# Power_FPGA.net
KiCad netlist of a schematic drawn in Altium Designer
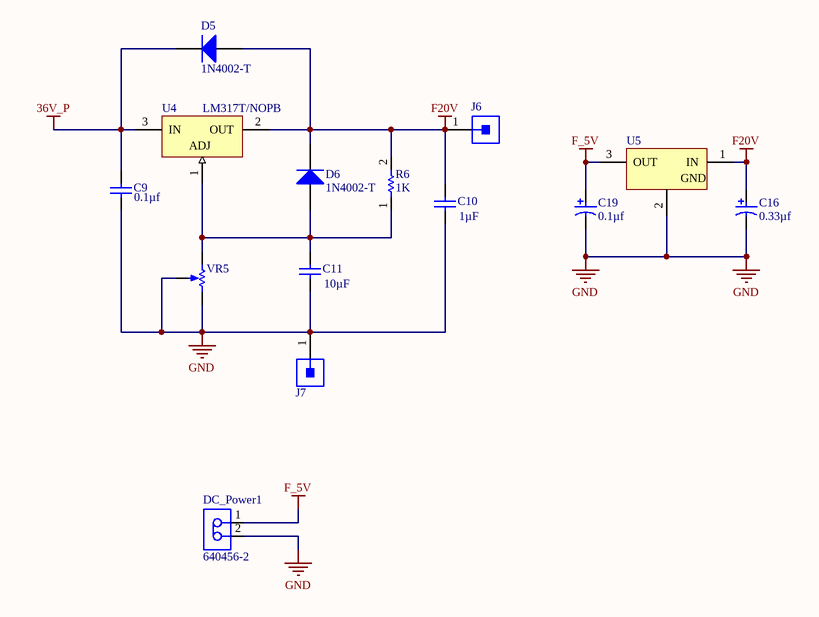
[diagram p0: Power_FPGA.SchDoc]

(export (version "E")
  (design (tool "Eeschema 10.0.6"))
  (components
    (comp (ref "C9")
      (value "0.1µf")
      (footprint "Cap-0.1uf-50V-Ceramic1")
      (description "Lead Capacitor X7R_EIA_ with Capacitance: 0.10F and Rated Voltage: 50Vdc")
      (fields (field (name "MP") "RDER71H104K0K1H03B") (field (name "MF") "Murata"))
      (libsource (lib "YAYAT-LIB") (part "Cap-0.1uf-50V-Ceramic_1"))
    )
    (comp (ref "C10")
      (value "K104K15X7RF5TL2")
      (footprint "Cap-0.1uf-50v-ceramic")
      (description "Ceramic Capacitor, 100 nF, +/- 10%, 50 V, -55 to 125 degC, 2-Pin THD, RoHS, Tape and Reel")
      (fields
        (field (name "MANUFACTURER") "Vishay")
        (field (name "TOLERANCE") "±10%")
        (field (name "CAPACITANCE") "1µF")
      )
      (libsource (lib "YAYAT-LIB") (part "Cap-0.1uf-50v-ceramic"))
    )
    (comp (ref "C11")
      (value "K104K15X7RF5TL2")
      (footprint "Cap-0.1uf-50v-ceramic")
      (description "Ceramic Capacitor, 100 nF, +/- 10%, 50 V, -55 to 125 degC, 2-Pin THD, RoHS, Tape and Reel")
      (fields
        (field (name "MANUFACTURER") "Vishay")
        (field (name "TOLERANCE") "±10%")
        (field (name "CAPACITANCE") "10µF")
      )
      (libsource (lib "YAYAT-LIB") (part "Cap-0.1uf-50v-ceramic"))
    )
    (comp (ref "C16")
      (value "0.33µf")
      (footprint "Cap-1uf-50v-radial")
      (description "Aluminum Electrolytic Capacitor, 1 uF, +/- 20%, 50 V, -55 to 105 degC, 2-Pin THD, RoHS, Bulk")
      (libsource (lib "YAYAT-LIB") (part "Cap-1uf-50v-radial"))
    )
    (comp (ref "C19")
      (value "0.1µf")
      (footprint "Cap-1uf-50v-radial")
      (description "Aluminum Electrolytic Capacitor, 1 uF, +/- 20%, 50 V, -55 to 105 degC, 2-Pin THD, RoHS, Bulk")
      (libsource (lib "YAYAT-LIB") (part "Cap-1uf-50v-radial"))
    )
    (comp (ref "D5")
      (value "1N4002-T")
      (footprint "Diode-1N4002")
      (description "1.0 A Rectifier, 15 pF, 100 V, -65 to 150 degC, 2-Pin DO-41 Plastic, RoHS, Tape and Reel")
      (fields (field (name "MANUFACTURER") "Diodes Inc"))
      (libsource (lib "YAYAT-LIB") (part "Diode-1N4002"))
    )
    (comp (ref "D6")
      (value "1N4002-T")
      (footprint "Diode-1N4002")
      (description "1.0 A Rectifier, 15 pF, 100 V, -65 to 150 degC, 2-Pin DO-41 Plastic, RoHS, Tape and Reel")
      (fields (field (name "MANUFACTURER") "Diodes Inc"))
      (libsource (lib "YAYAT-LIB") (part "Diode-1N4002"))
    )
    (comp (ref "DC_Power1")
      (value "640456-2")
      (footprint "Conn-Wire-header-2pin")
      (fields (field (name "MANUFACTURER") "TE Connectivity"))
      (libsource (lib "YAYAT-LIB") (part "Conn-Wire-header-2pin"))
    )
    (comp (ref "J6")
      (value "61300111121")
      (footprint "PIN-HEADER-1PIN")
      (description "THT Vertical Pin Header WR-PHD, Pitch 2.54 mm, Single Row, 1 pins")
      (fields (field (name "MANUFACTURER") "Wurth Elektronik") (field (name "PUBLISHER") "WurthElektronik"))
      (libsource (lib "") (part "Pin-Header-1Pin_1"))
    )
    (comp (ref "J7")
      (value "61300111121")
      (footprint "PIN-HEADER-1PIN")
      (description "THT Vertical Pin Header WR-PHD, Pitch 2.54 mm, Single Row, 1 pins")
      (fields (field (name "MANUFACTURER") "Wurth Elektronik") (field (name "PUBLISHER") "WurthElektronik"))
      (libsource (lib "YAYAT-LIB") (part "Pin-Header-1Pin"))
    )
    (comp (ref "R6")
      (value "1K")
      (footprint "Resistor-1-Watt")
      (description "Resistor")
      (fields
        (field (name "MANUFACTURER_PART_NUMBER") "OK1025E-R52")
        (field (name "MOUSER PART NUMBER") "588-OK1025E-R52")
      )
      (libsource (lib "YAYAT-LIB") (part "Resistor-1-Watt"))
    )
    (comp (ref "U4")
      (value "LM317T/NOPB")
      (footprint "Voltage-Regulator-LM317")
      (description "3-Terminal Adjustable Regulator, 3-pin TO-220, Pb-Free")
      (fields (field (name "MANUFACTURER") "Texas Instruments"))
      (libsource (lib "YAYAT-LIB") (part "Voltage-Regulator-LM317"))
    )
    (comp (ref "U5")
      (value "L7805ACV")
      (footprint "Voltage-Regulator-L7805ACV")
      (description "Positive Voltage Regulator, 5V, 3-Pin TO-220")
      (libsource (lib "YAYAT-LIB") (part "Voltage-Regulator-L7805ACV"))
    )
    (comp (ref "VR5")
      (value "3296W-1-103LF")
      (footprint "Resistor-Trimmer")
      (fields (field (name "TOLERANCE") "1%"))
      (libsource (lib "YAYAT-LIB") (part "Resistor-Trimmer"))
    )
  )
  (nets
    (net (code "1") (name "36V_P") (class "Default")
      (node (ref "C9") (pin "2") (pinfunction "2_2") (pintype "passive"))
      (node (ref "D5") (pin "2") (pinfunction "K_2") (pintype "passive"))
      (node (ref "U4") (pin "3") (pinfunction "IN_3") (pintype "power_in"))
    )
    (net (code "2") (name "F20V") (class "Default")
      (node (ref "C10") (pin "2") (pinfunction "2_2") (pintype "passive"))
      (node (ref "C16") (pin "1") (pinfunction "1_1") (pintype "passive"))
      (node (ref "D5") (pin "1") (pinfunction "A_1") (pintype "passive"))
      (node (ref "D6") (pin "2") (pinfunction "K_2") (pintype "passive"))
      (node (ref "J6") (pin "1") (pinfunction "1_1") (pintype "passive"))
      (node (ref "R6") (pin "2") (pinfunction "2_2") (pintype "passive"))
      (node (ref "U4") (pin "2") (pinfunction "OUT_2") (pintype "power_in"))
      (node (ref "U5") (pin "1") (pinfunction "IN_1") (pintype "power_in"))
    )
    (net (code "3") (name "F_5V") (class "Default")
      (node (ref "C19") (pin "1") (pinfunction "1_1") (pintype "passive"))
      (node (ref "DC_Power1") (pin "1") (pinfunction "1_1") (pintype "passive"))
      (node (ref "U5") (pin "3") (pinfunction "OUT_3") (pintype "power_in"))
    )
    (net (code "4") (name "GND") (class "Default")
      (node (ref "C10") (pin "1") (pinfunction "1_1") (pintype "passive"))
      (node (ref "C11") (pin "1") (pinfunction "1_1") (pintype "passive"))
      (node (ref "C16") (pin "2") (pinfunction "2_2") (pintype "passive"))
      (node (ref "C19") (pin "2") (pinfunction "2_2") (pintype "passive"))
      (node (ref "C9") (pin "1") (pinfunction "1_1") (pintype "passive"))
      (node (ref "DC_Power1") (pin "2") (pinfunction "2_2") (pintype "passive"))
      (node (ref "J7") (pin "1") (pinfunction "1_1") (pintype "passive"))
      (node (ref "U5") (pin "2") (pinfunction "GND_2") (pintype "power_in"))
      (node (ref "VR5") (pin "2") (pinfunction "S_2") (pintype "passive"))
      (node (ref "VR5") (pin "3") (pinfunction "CW_3") (pintype "passive"))
    )
    (net (code "5") (name "Net-(D6-A)") (class "Default")
      (node (ref "C11") (pin "2") (pinfunction "2_2") (pintype "passive"))
      (node (ref "D6") (pin "1") (pinfunction "A_1") (pintype "passive"))
      (node (ref "R6") (pin "1") (pinfunction "1_1") (pintype "passive"))
      (node (ref "U4") (pin "1") (pinfunction "ADJ_1") (pintype "input"))
      (node (ref "VR5") (pin "1") (pinfunction "CCW_1") (pintype "passive"))
    )
  )
)
